# Microcontroller.net
KiCad netlist of a schematic drawn in Altium Designer
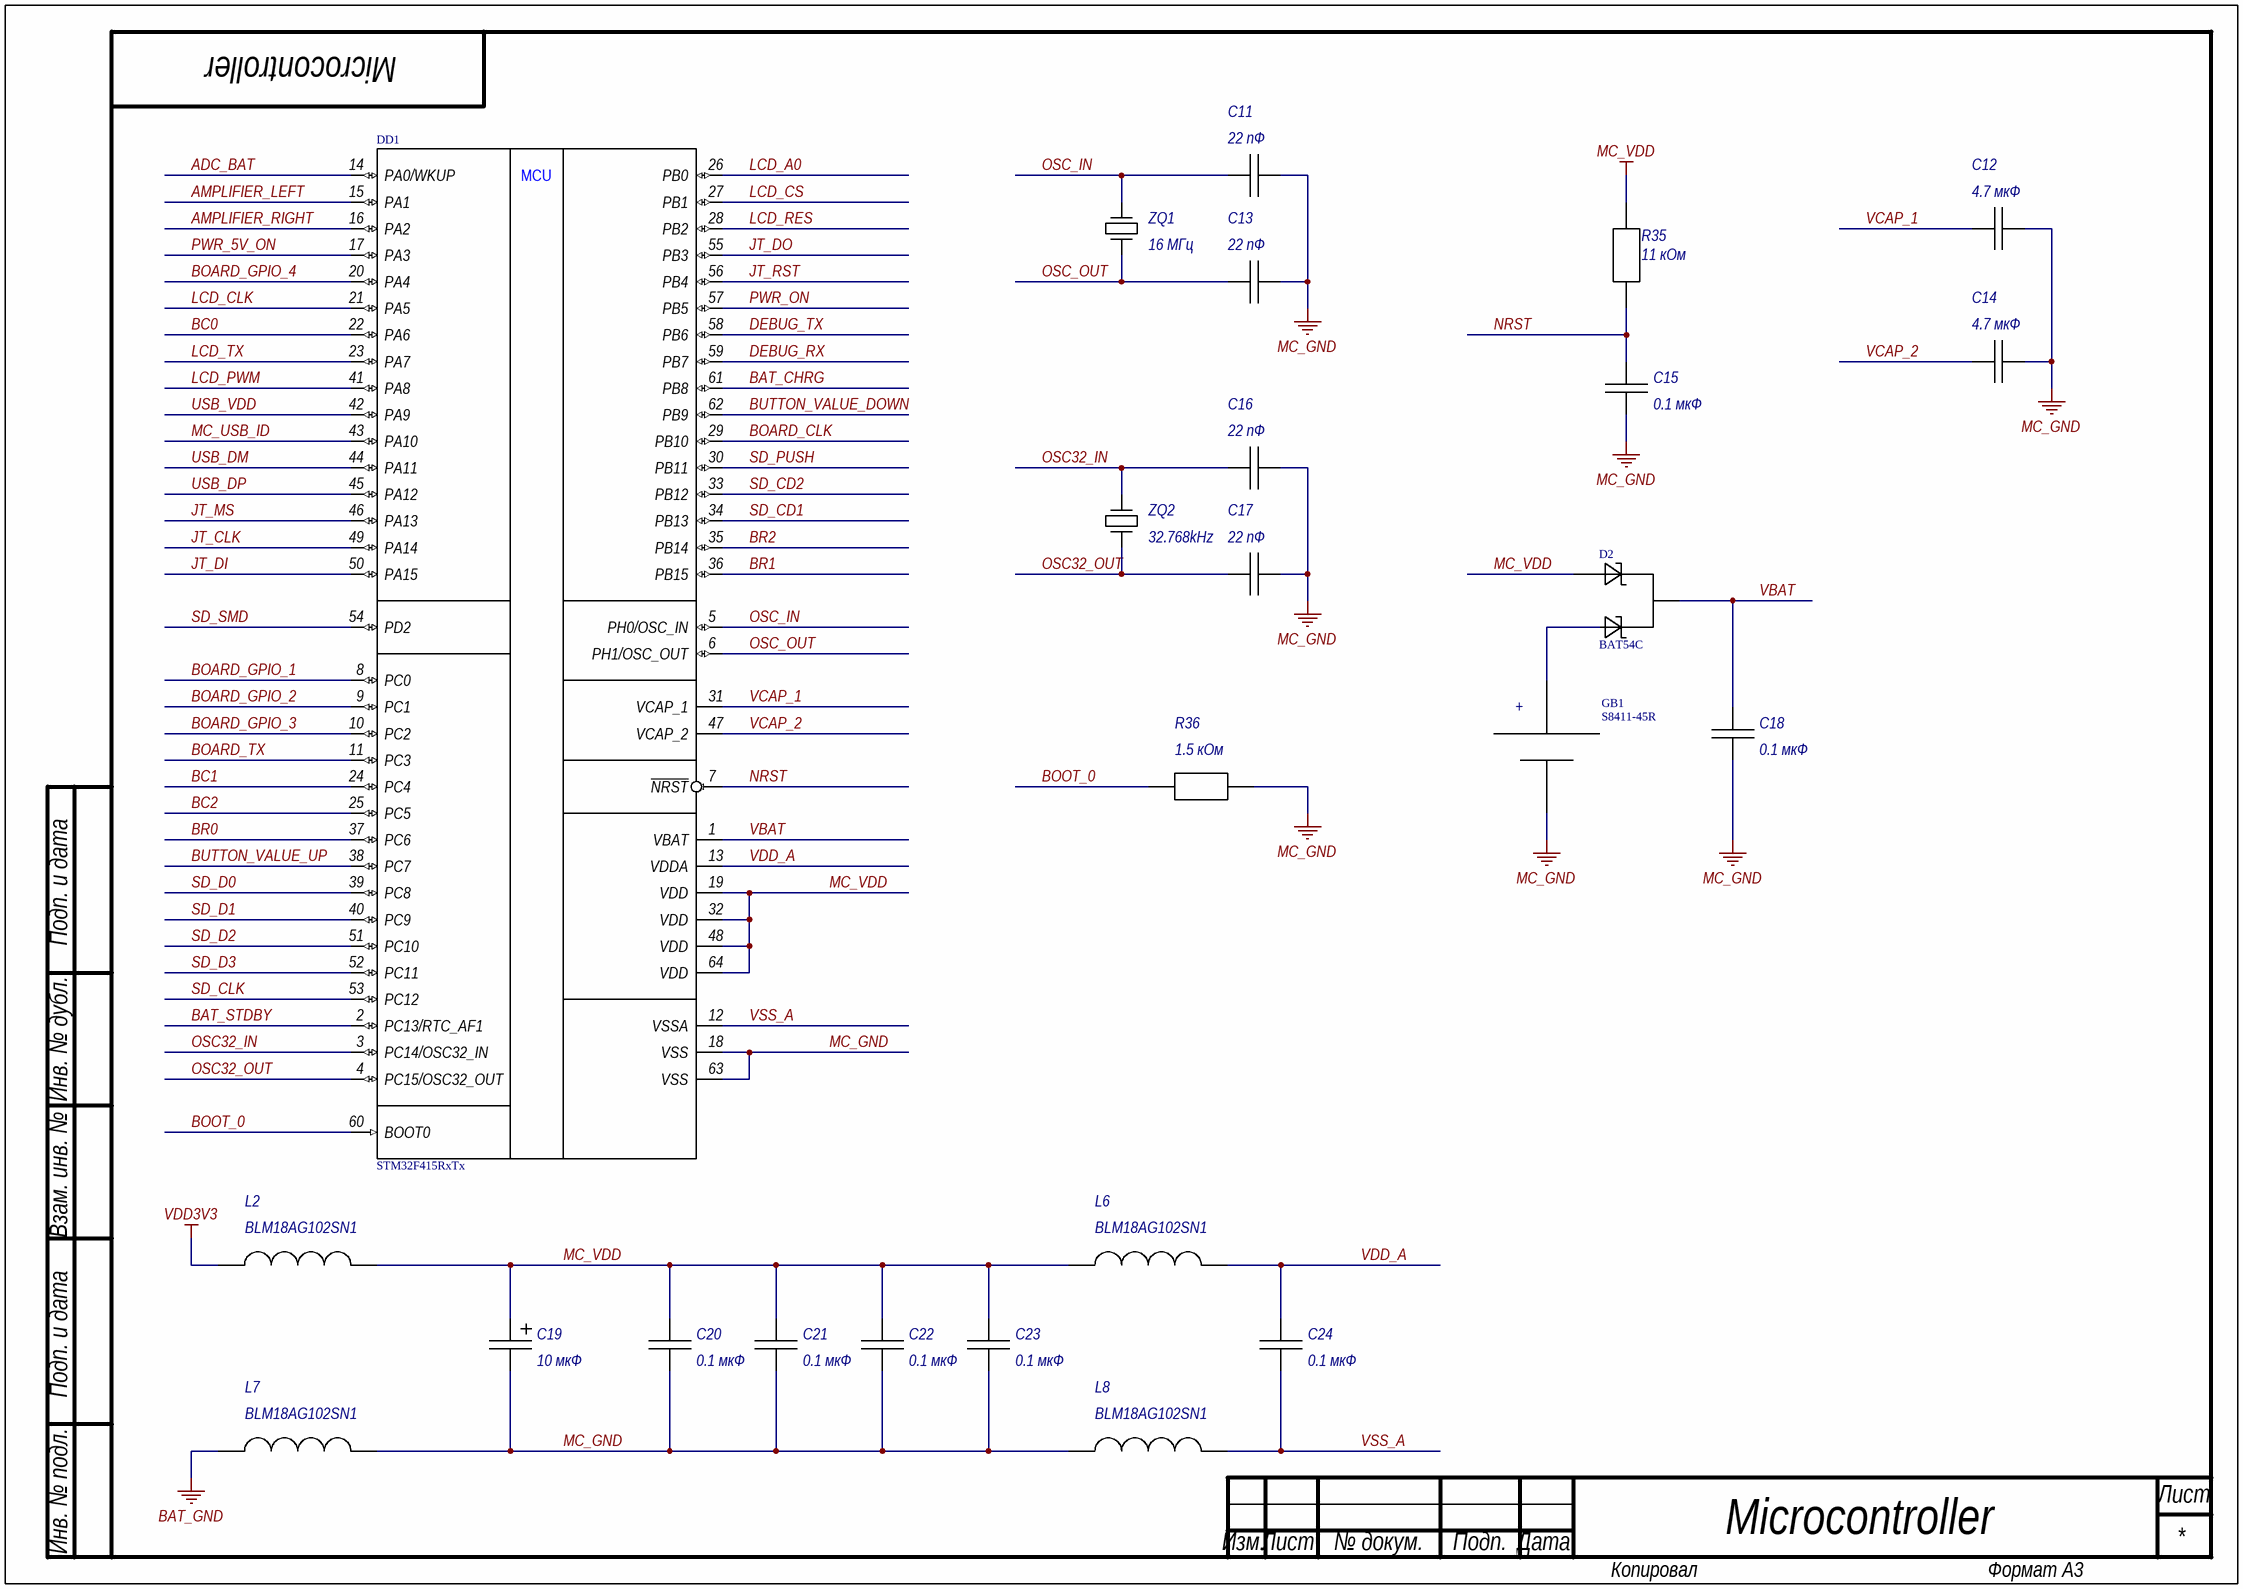
[diagram p0: Microcontroller.SchDoc]

(export (version "E")
  (design (tool "Eeschema 10.0.6"))
  (components
    (comp (ref "C11")
      (value "22 пФ")
      (footprint "C 0805")
      (description "SMD Capacitor 0805")
      (fields
        (field (name "TOLERANCE") "/Укажите допуск в процентах/")
        (field (name "MANUFACTURER") "/Укажите компанию-производителя/")
      )
      (libsource (lib "my_lib") (part "CAP 0805"))
    )
    (comp (ref "C12")
      (value "4.7 мкФ")
      (footprint "C 0805")
      (description "SMD Capacitor 0805")
      (fields
        (field (name "TOLERANCE") "/Укажите допуск в процентах/")
        (field (name "MANUFACTURER") "/Укажите компанию-производителя/")
      )
      (libsource (lib "my_lib") (part "CAP 0805"))
    )
    (comp (ref "C13")
      (value "22 пФ")
      (footprint "C 0805")
      (description "SMD Capacitor 0805")
      (fields
        (field (name "TOLERANCE") "/Укажите допуск в процентах/")
        (field (name "MANUFACTURER") "/Укажите компанию-производителя/")
      )
      (libsource (lib "my_lib") (part "CAP 0805"))
    )
    (comp (ref "C14")
      (value "4.7 мкФ")
      (footprint "C 0805")
      (description "SMD Capacitor 0805")
      (fields
        (field (name "TOLERANCE") "/Укажите допуск в процентах/")
        (field (name "MANUFACTURER") "/Укажите компанию-производителя/")
      )
      (libsource (lib "my_lib") (part "CAP 0805"))
    )
    (comp (ref "C15")
      (value "0.1 мкФ")
      (footprint "C 0805")
      (description "SMD Capacitor 0805")
      (fields
        (field (name "TOLERANCE") "/Укажите допуск в процентах/")
        (field (name "MANUFACTURER") "/Укажите компанию-производителя/")
      )
      (libsource (lib "my_lib") (part "CAP 0805"))
    )
    (comp (ref "C16")
      (value "22 пФ")
      (footprint "C 0805")
      (description "SMD Capacitor 0805")
      (fields
        (field (name "TOLERANCE") "/Укажите допуск в процентах/")
        (field (name "MANUFACTURER") "/Укажите компанию-производителя/")
      )
      (libsource (lib "my_lib") (part "CAP 0805"))
    )
    (comp (ref "C17")
      (value "22 пФ")
      (footprint "C 0805")
      (description "SMD Capacitor 0805")
      (fields
        (field (name "TOLERANCE") "/Укажите допуск в процентах/")
        (field (name "MANUFACTURER") "/Укажите компанию-производителя/")
      )
      (libsource (lib "my_lib") (part "CAP 0805"))
    )
    (comp (ref "C18")
      (value "0.1 мкФ")
      (footprint "C 0805")
      (description "SMD Capacitor 0805")
      (fields
        (field (name "TOLERANCE") "/Укажите допуск в процентах/")
        (field (name "MANUFACTURER") "/Укажите компанию-производителя/")
      )
      (libsource (lib "my_lib") (part "CAP 0805"))
    )
    (comp (ref "C19")
      (value "10 мкФ")
      (footprint "C TAN_A")
      (description "SMD Tantalium Capacitor A")
      (libsource (lib "my_lib") (part "CAP TAN_A"))
    )
    (comp (ref "C20")
      (value "0.1 мкФ")
      (footprint "C 0805")
      (description "SMD Capacitor 0805")
      (fields
        (field (name "TOLERANCE") "/Укажите допуск в процентах/")
        (field (name "MANUFACTURER") "/Укажите компанию-производителя/")
      )
      (libsource (lib "my_lib") (part "CAP 0805"))
    )
    (comp (ref "C21")
      (value "0.1 мкФ")
      (footprint "C 0805")
      (description "SMD Capacitor 0805")
      (fields
        (field (name "TOLERANCE") "/Укажите допуск в процентах/")
        (field (name "MANUFACTURER") "/Укажите компанию-производителя/")
      )
      (libsource (lib "my_lib") (part "CAP 0805"))
    )
    (comp (ref "C22")
      (value "0.1 мкФ")
      (footprint "C 0805")
      (description "SMD Capacitor 0805")
      (fields
        (field (name "TOLERANCE") "/Укажите допуск в процентах/")
        (field (name "MANUFACTURER") "/Укажите компанию-производителя/")
      )
      (libsource (lib "my_lib") (part "CAP 0805"))
    )
    (comp (ref "C23")
      (value "0.1 мкФ")
      (footprint "C 0805")
      (description "SMD Capacitor 0805")
      (fields
        (field (name "TOLERANCE") "/Укажите допуск в процентах/")
        (field (name "MANUFACTURER") "/Укажите компанию-производителя/")
      )
      (libsource (lib "my_lib") (part "CAP 0805"))
    )
    (comp (ref "C24")
      (value "0.1 мкФ")
      (footprint "C 0805")
      (description "SMD Capacitor 0805")
      (fields
        (field (name "TOLERANCE") "/Укажите допуск в процентах/")
        (field (name "MANUFACTURER") "/Укажите компанию-производителя/")
      )
      (libsource (lib "my_lib") (part "CAP 0805"))
    )
    (comp (ref "D2") (value "BAT54C") (footprint "SOT-23") (libsource (lib "my_lib") (part "BAT54C")))
    (comp (ref "DD1")
      (value "STM32F415RxTx")
      (footprint "LQFP64")
      (libsource (lib "my_lib") (part "STM32F415RxTx"))
    )
    (comp (ref "GB1")
      (value "S8411-45R")
      (footprint "S8411-45R")
      (libsource (lib "my_lib") (part "S8411-45R"))
    )
    (comp (ref "L2")
      (value "BLM18AG102SN1")
      (footprint "FB 0603")
      (libsource (lib "my_lib") (part "BLM18AG102SN1"))
    )
    (comp (ref "L6")
      (value "BLM18AG102SN1")
      (footprint "FB 0603")
      (libsource (lib "my_lib") (part "BLM18AG102SN1"))
    )
    (comp (ref "L7")
      (value "BLM18AG102SN1")
      (footprint "FB 0603")
      (libsource (lib "my_lib") (part "BLM18AG102SN1"))
    )
    (comp (ref "L8")
      (value "BLM18AG102SN1")
      (footprint "FB 0603")
      (libsource (lib "my_lib") (part "BLM18AG102SN1"))
    )
    (comp (ref "R35") (value "11 кОм") (footprint "RES 0402") (libsource (lib "my_lib") (part "RES 0402")))
    (comp (ref "R36") (value "1.5 кОм") (footprint "RES 0402") (libsource (lib "my_lib") (part "RES 0402")))
    (comp (ref "ZQ1")
      (value "16 МГц")
      (footprint "NX3225SA")
      (description "QUARTZ CRYSTAL")
      (fields (field (name "MANUFACTURER") "NDK") (field (name "Comment") "NX3225SA-16.000M-STD-CRS-2"))
      (libsource (lib "my_lib") (part "NX3225SA-16.000M-STD-CRS-2"))
    )
    (comp (ref "ZQ2")
      (value "32.768kHz")
      (footprint "MC-306")
      (description "QUARTZ CRYSTAL")
      (fields (field (name "Comment") "MC-306"))
      (libsource (lib "my_lib") (part "MC-306"))
    )
  )
  (nets
    (net (code "1") (name "/ADC_BAT") (class "Default")
      (node (ref "DD1") (pin "14") (pinfunction "PA0/WKUP_14") (pintype "bidirectional"))
    )
    (net (code "2") (name "/AMPLIFIER_LEFT") (class "Default")
      (node (ref "DD1") (pin "15") (pinfunction "PA1_15") (pintype "bidirectional"))
    )
    (net (code "3") (name "/AMPLIFIER_RIGHT") (class "Default")
      (node (ref "DD1") (pin "16") (pinfunction "PA2_16") (pintype "bidirectional"))
    )
    (net (code "4") (name "/BAT_CHRG") (class "Default")
      (node (ref "DD1") (pin "61") (pinfunction "PB8_61") (pintype "bidirectional"))
    )
    (net (code "5") (name "/BAT_STDBY") (class "Default")
      (node (ref "DD1") (pin "2") (pinfunction "PC13/RTC_AF1_2") (pintype "bidirectional"))
    )
    (net (code "6") (name "/BC0") (class "Default")
      (node (ref "DD1") (pin "22") (pinfunction "PA6_22") (pintype "bidirectional"))
    )
    (net (code "7") (name "/BC1") (class "Default")
      (node (ref "DD1") (pin "24") (pinfunction "PC4_24") (pintype "bidirectional"))
    )
    (net (code "8") (name "/BC2") (class "Default")
      (node (ref "DD1") (pin "25") (pinfunction "PC5_25") (pintype "bidirectional"))
    )
    (net (code "9") (name "/BOARD_CLK") (class "Default")
      (node (ref "DD1") (pin "29") (pinfunction "PB10_29") (pintype "bidirectional"))
    )
    (net (code "10") (name "/BOARD_GPIO_1") (class "Default")
      (node (ref "DD1") (pin "8") (pinfunction "PC0_8") (pintype "bidirectional"))
    )
    (net (code "11") (name "/BOARD_GPIO_2") (class "Default")
      (node (ref "DD1") (pin "9") (pinfunction "PC1_9") (pintype "bidirectional"))
    )
    (net (code "12") (name "/BOARD_GPIO_3") (class "Default")
      (node (ref "DD1") (pin "10") (pinfunction "PC2_10") (pintype "bidirectional"))
    )
    (net (code "13") (name "/BOARD_GPIO_4") (class "Default")
      (node (ref "DD1") (pin "20") (pinfunction "PA4_20") (pintype "bidirectional"))
    )
    (net (code "14") (name "/BOARD_TX") (class "Default")
      (node (ref "DD1") (pin "11") (pinfunction "PC3_11") (pintype "bidirectional"))
    )
    (net (code "15") (name "/BOOT_0") (class "Default")
      (node (ref "DD1") (pin "60") (pinfunction "BOOT0_60") (pintype "input"))
      (node (ref "R36") (pin "2") (pinfunction "2_2") (pintype "passive"))
    )
    (net (code "16") (name "/BR0") (class "Default")
      (node (ref "DD1") (pin "37") (pinfunction "PC6_37") (pintype "bidirectional"))
    )
    (net (code "17") (name "/BR1") (class "Default")
      (node (ref "DD1") (pin "36") (pinfunction "PB15_36") (pintype "bidirectional"))
    )
    (net (code "18") (name "/BR2") (class "Default")
      (node (ref "DD1") (pin "35") (pinfunction "PB14_35") (pintype "bidirectional"))
    )
    (net (code "19") (name "/BUTTON_VALUE_DOWN") (class "Default")
      (node (ref "DD1") (pin "62") (pinfunction "PB9_62") (pintype "bidirectional"))
    )
    (net (code "20") (name "/BUTTON_VALUE_UP") (class "Default")
      (node (ref "DD1") (pin "38") (pinfunction "PC7_38") (pintype "bidirectional"))
    )
    (net (code "21") (name "/DEBUG_RX") (class "Default")
      (node (ref "DD1") (pin "59") (pinfunction "PB7_59") (pintype "bidirectional"))
    )
    (net (code "22") (name "/DEBUG_TX") (class "Default")
      (node (ref "DD1") (pin "58") (pinfunction "PB6_58") (pintype "bidirectional"))
    )
    (net (code "23") (name "/JT_CLK") (class "Default")
      (node (ref "DD1") (pin "49") (pinfunction "PA14_49") (pintype "bidirectional"))
    )
    (net (code "24") (name "/JT_DI") (class "Default")
      (node (ref "DD1") (pin "50") (pinfunction "PA15_50") (pintype "bidirectional"))
    )
    (net (code "25") (name "/JT_DO") (class "Default")
      (node (ref "DD1") (pin "55") (pinfunction "PB3_55") (pintype "bidirectional"))
    )
    (net (code "26") (name "/JT_MS") (class "Default")
      (node (ref "DD1") (pin "46") (pinfunction "PA13_46") (pintype "bidirectional"))
    )
    (net (code "27") (name "/JT_RST") (class "Default")
      (node (ref "DD1") (pin "56") (pinfunction "PB4_56") (pintype "bidirectional"))
    )
    (net (code "28") (name "/LCD_A0") (class "Default")
      (node (ref "DD1") (pin "26") (pinfunction "PB0_26") (pintype "bidirectional"))
    )
    (net (code "29") (name "/LCD_CLK") (class "Default")
      (node (ref "DD1") (pin "21") (pinfunction "PA5_21") (pintype "bidirectional"))
    )
    (net (code "30") (name "/LCD_CS") (class "Default")
      (node (ref "DD1") (pin "27") (pinfunction "PB1_27") (pintype "bidirectional"))
    )
    (net (code "31") (name "/LCD_PWM") (class "Default")
      (node (ref "DD1") (pin "41") (pinfunction "PA8_41") (pintype "bidirectional"))
    )
    (net (code "32") (name "/LCD_RES") (class "Default")
      (node (ref "DD1") (pin "28") (pinfunction "PB2_28") (pintype "bidirectional"))
    )
    (net (code "33") (name "/LCD_TX") (class "Default")
      (node (ref "DD1") (pin "23") (pinfunction "PA7_23") (pintype "bidirectional"))
    )
    (net (code "34") (name "/MC_USB_ID") (class "Default")
      (node (ref "DD1") (pin "43") (pinfunction "PA10_43") (pintype "bidirectional"))
    )
    (net (code "35") (name "/NRST") (class "Default")
      (node (ref "C15") (pin "2") (pinfunction "2_2") (pintype "passive"))
      (node (ref "DD1") (pin "7") (pinfunction "~{NRST}_7") (pintype "input"))
      (node (ref "R35") (pin "2") (pinfunction "2_2") (pintype "passive"))
    )
    (net (code "36") (name "/OSC32_IN") (class "Default")
      (node (ref "C16") (pin "1") (pinfunction "1_1") (pintype "passive"))
      (node (ref "DD1") (pin "3") (pinfunction "PC14/OSC32_IN_3") (pintype "bidirectional"))
      (node (ref "ZQ2") (pin "4") (pinfunction "XO_4") (pintype "passive"))
    )
    (net (code "37") (name "/OSC32_OUT") (class "Default")
      (node (ref "C17") (pin "1") (pinfunction "1_1") (pintype "passive"))
      (node (ref "DD1") (pin "4") (pinfunction "PC15/OSC32_OUT_4") (pintype "bidirectional"))
      (node (ref "ZQ2") (pin "1") (pinfunction "XI_1") (pintype "passive"))
    )
    (net (code "38") (name "/OSC_IN") (class "Default")
      (node (ref "C11") (pin "1") (pinfunction "1_1") (pintype "passive"))
      (node (ref "DD1") (pin "5") (pinfunction "PH0/OSC_IN_5") (pintype "bidirectional"))
      (node (ref "ZQ1") (pin "3") (pinfunction "XO_3") (pintype "passive"))
    )
    (net (code "39") (name "/OSC_OUT") (class "Default")
      (node (ref "C13") (pin "1") (pinfunction "1_1") (pintype "passive"))
      (node (ref "DD1") (pin "6") (pinfunction "PH1/OSC_OUT_6") (pintype "bidirectional"))
      (node (ref "ZQ1") (pin "1") (pinfunction "XI_1") (pintype "passive"))
    )
    (net (code "40") (name "/PWR_5V_ON") (class "Default")
      (node (ref "DD1") (pin "17") (pinfunction "PA3_17") (pintype "bidirectional"))
    )
    (net (code "41") (name "/PWR_ON") (class "Default")
      (node (ref "DD1") (pin "57") (pinfunction "PB5_57") (pintype "bidirectional"))
    )
    (net (code "42") (name "/SD_CD1") (class "Default")
      (node (ref "DD1") (pin "34") (pinfunction "PB13_34") (pintype "bidirectional"))
    )
    (net (code "43") (name "/SD_CD2") (class "Default")
      (node (ref "DD1") (pin "33") (pinfunction "PB12_33") (pintype "bidirectional"))
    )
    (net (code "44") (name "/SD_CLK") (class "Default")
      (node (ref "DD1") (pin "53") (pinfunction "PC12_53") (pintype "bidirectional"))
    )
    (net (code "45") (name "/SD_D0") (class "Default")
      (node (ref "DD1") (pin "39") (pinfunction "PC8_39") (pintype "bidirectional"))
    )
    (net (code "46") (name "/SD_D1") (class "Default")
      (node (ref "DD1") (pin "40") (pinfunction "PC9_40") (pintype "bidirectional"))
    )
    (net (code "47") (name "/SD_D2") (class "Default")
      (node (ref "DD1") (pin "51") (pinfunction "PC10_51") (pintype "bidirectional"))
    )
    (net (code "48") (name "/SD_D3") (class "Default")
      (node (ref "DD1") (pin "52") (pinfunction "PC11_52") (pintype "bidirectional"))
    )
    (net (code "49") (name "/SD_PUSH") (class "Default")
      (node (ref "DD1") (pin "30") (pinfunction "PB11_30") (pintype "bidirectional"))
    )
    (net (code "50") (name "/SD_SMD") (class "Default")
      (node (ref "DD1") (pin "54") (pinfunction "PD2_54") (pintype "bidirectional"))
    )
    (net (code "51") (name "/USB_DM") (class "Default")
      (node (ref "DD1") (pin "44") (pinfunction "PA11_44") (pintype "bidirectional"))
    )
    (net (code "52") (name "/USB_DP") (class "Default")
      (node (ref "DD1") (pin "45") (pinfunction "PA12_45") (pintype "bidirectional"))
    )
    (net (code "53") (name "/USB_VDD") (class "Default")
      (node (ref "DD1") (pin "42") (pinfunction "PA9_42") (pintype "bidirectional"))
    )
    (net (code "54") (name "/VBAT") (class "Default")
      (node (ref "C18") (pin "1") (pinfunction "1_1") (pintype "passive"))
      (node (ref "D2") (pin "3") (pinfunction "3_3") (pintype "passive"))
      (node (ref "DD1") (pin "1") (pinfunction "VBAT_1") (pintype "power_in"))
    )
    (net (code "55") (name "/VCAP_1") (class "Default")
      (node (ref "C12") (pin "1") (pinfunction "1_1") (pintype "passive"))
      (node (ref "DD1") (pin "31") (pinfunction "VCAP_1_31") (pintype "power_in"))
    )
    (net (code "56") (name "/VCAP_2") (class "Default")
      (node (ref "C14") (pin "1") (pinfunction "1_1") (pintype "passive"))
      (node (ref "DD1") (pin "47") (pinfunction "VCAP_2_47") (pintype "power_in"))
    )
    (net (code "57") (name "/VDD_A") (class "Default")
      (node (ref "C24") (pin "1") (pinfunction "1_1") (pintype "passive"))
      (node (ref "DD1") (pin "13") (pinfunction "VDDA_13") (pintype "power_in"))
      (node (ref "L6") (pin "2") (pinfunction "2_2") (pintype "passive"))
    )
    (net (code "58") (name "/VSS_A") (class "Default")
      (node (ref "C24") (pin "2") (pinfunction "2_2") (pintype "passive"))
      (node (ref "DD1") (pin "12") (pinfunction "VSSA_12") (pintype "power_in"))
      (node (ref "L8") (pin "2") (pinfunction "2_2") (pintype "passive"))
    )
    (net (code "59") (name "BAT_GND") (class "Default")
      (node (ref "L7") (pin "1") (pinfunction "1_1") (pintype "passive"))
    )
    (net (code "60") (name "MC_GND") (class "Default")
      (node (ref "C11") (pin "2") (pinfunction "2_2") (pintype "passive"))
      (node (ref "C12") (pin "2") (pinfunction "2_2") (pintype "passive"))
      (node (ref "C13") (pin "2") (pinfunction "2_2") (pintype "passive"))
      (node (ref "C14") (pin "2") (pinfunction "2_2") (pintype "passive"))
      (node (ref "C15") (pin "1") (pinfunction "1_1") (pintype "passive"))
      (node (ref "C16") (pin "2") (pinfunction "2_2") (pintype "passive"))
      (node (ref "C17") (pin "2") (pinfunction "2_2") (pintype "passive"))
      (node (ref "C18") (pin "2") (pinfunction "2_2") (pintype "passive"))
      (node (ref "C19") (pin "2") (pinfunction "2_2") (pintype "passive"))
      (node (ref "C20") (pin "2") (pinfunction "2_2") (pintype "passive"))
      (node (ref "C21") (pin "2") (pinfunction "2_2") (pintype "passive"))
      (node (ref "C22") (pin "2") (pinfunction "2_2") (pintype "passive"))
      (node (ref "C23") (pin "2") (pinfunction "2_2") (pintype "passive"))
      (node (ref "DD1") (pin "18") (pinfunction "VSS_18") (pintype "power_in"))
      (node (ref "DD1") (pin "63") (pinfunction "VSS_63") (pintype "power_in"))
      (node (ref "GB1") (pin "2") (pinfunction "2_2") (pintype "passive"))
      (node (ref "L7") (pin "2") (pinfunction "2_2") (pintype "passive"))
      (node (ref "L8") (pin "1") (pinfunction "1_1") (pintype "passive"))
      (node (ref "R36") (pin "1") (pinfunction "1_1") (pintype "passive"))
    )
    (net (code "61") (name "MC_VDD") (class "Default")
      (node (ref "C19") (pin "1") (pinfunction "1_1") (pintype "passive"))
      (node (ref "C20") (pin "1") (pinfunction "1_1") (pintype "passive"))
      (node (ref "C21") (pin "1") (pinfunction "1_1") (pintype "passive"))
      (node (ref "C22") (pin "1") (pinfunction "1_1") (pintype "passive"))
      (node (ref "C23") (pin "1") (pinfunction "1_1") (pintype "passive"))
      (node (ref "D2") (pin "2") (pinfunction "2_2") (pintype "passive"))
      (node (ref "DD1") (pin "19") (pinfunction "VDD_19") (pintype "power_in"))
      (node (ref "DD1") (pin "32") (pinfunction "VDD_32") (pintype "power_in"))
      (node (ref "DD1") (pin "48") (pinfunction "VDD_48") (pintype "power_in"))
      (node (ref "DD1") (pin "64") (pinfunction "VDD_64") (pintype "power_in"))
      (node (ref "L2") (pin "2") (pinfunction "2_2") (pintype "passive"))
      (node (ref "L6") (pin "1") (pinfunction "1_1") (pintype "passive"))
      (node (ref "R35") (pin "1") (pinfunction "1_1") (pintype "passive"))
    )
    (net (code "62") (name "Net-(D2-Pad1)") (class "Default")
      (node (ref "D2") (pin "1") (pinfunction "1_1") (pintype "passive"))
      (node (ref "GB1") (pin "1") (pinfunction "1_1") (pintype "passive"))
    )
    (net (code "63") (name "VDD3V3") (class "Default")
      (node (ref "L2") (pin "1") (pinfunction "1_1") (pintype "passive"))
    )
    (net (code "64") (name "unconnected-(ZQ1-NC-Pad2)") (class "Default")
      (node (ref "ZQ1") (pin "2") (pinfunction "NC_2") (pintype "passive"))
    )
    (net (code "65") (name "unconnected-(ZQ1-NC-Pad4)") (class "Default")
      (node (ref "ZQ1") (pin "4") (pinfunction "NC_4") (pintype "passive"))
    )
    (net (code "66") (name "unconnected-(ZQ2-NC-Pad2)") (class "Default")
      (node (ref "ZQ2") (pin "2") (pinfunction "NC_2") (pintype "passive"))
    )
    (net (code "67") (name "unconnected-(ZQ2-NC-Pad4)") (class "Default")
      (node (ref "ZQ2") (pin "4") (pinfunction "NC_4") (pintype "passive"))
    )
  )
)
